# Glove_PCB.net
KiCad netlist of a schematic drawn in Altium Designer
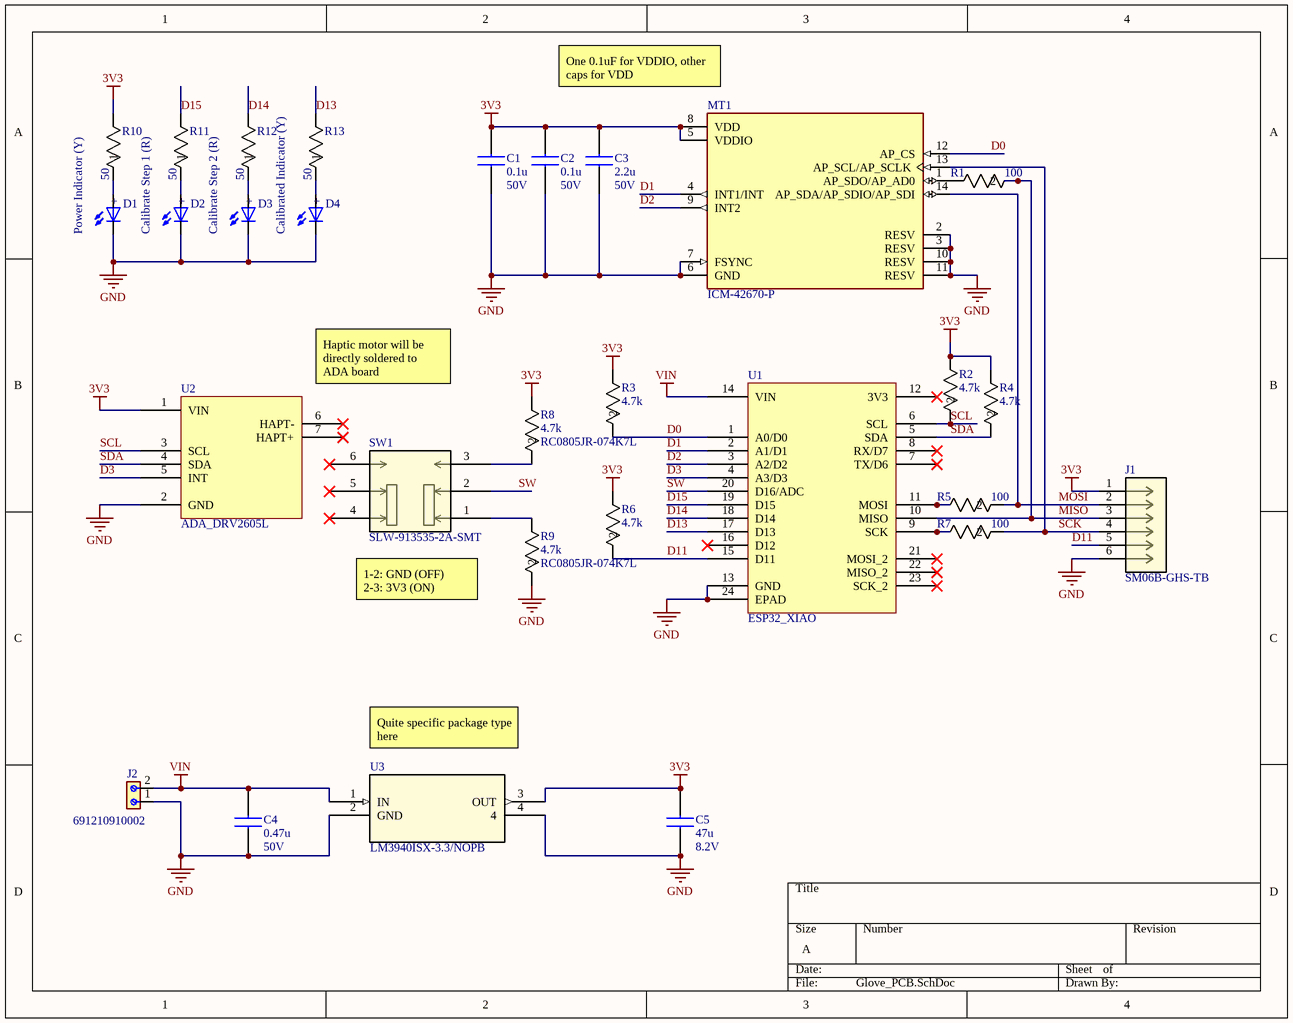
[diagram p0: Glove_PCB.SchDoc]

(export (version "E")
  (design (tool "Eeschema 10.0.6"))
  (components
    (comp (ref "C1")
      (value "0.1u")
      (footprint "CAPC2012X145N")
      (description "Multilayer Ceramic Chip Capacitors, Capacitance=0.1u")
      (fields
        (field (name "MANUFACTURER_PART_NUMBER") "KAM21BR71H104JM")
        (field (name "RATED VOLTAGE") "50V")
      )
      (libsource (lib "Caps") (part "KAM21BR71H104JM"))
    )
    (comp (ref "C2")
      (value "0.1u")
      (footprint "CAPC2012X145N")
      (description "Multilayer Ceramic Chip Capacitors, Capacitance=0.1u")
      (fields
        (field (name "MANUFACTURER_PART_NUMBER") "KAM21BR71H104JM")
        (field (name "RATED VOLTAGE") "50V")
      )
      (libsource (lib "Caps") (part "KAM21BR71H104JM"))
    )
    (comp (ref "C3")
      (value "2.2u")
      (footprint "CAPC2012X145N")
      (description "Multilayer Ceramic Chip Capacitors, Capacitance=2.2u")
      (fields
        (field (name "MANUFACTURER_PART_NUMBER") "C2012X7R1H225K125AE")
        (field (name "RATED VOLTAGE") "50V")
      )
      (libsource (lib "Caps") (part "C2012X7R1H225K125AE"))
    )
    (comp (ref "C4")
      (value "0.47u")
      (footprint "CAPC2012X145N")
      (description "Multilayer Ceramic Chip Capacitors, Capacitance=0.47u")
      (fields
        (field (name "MANUFACTURER_PART_NUMBER") "GCM21BR71H474KA55K")
        (field (name "RATED VOLTAGE") "50V")
      )
      (libsource (lib "Caps") (part "GCM21BR71H474KA55K"))
    )
    (comp (ref "C5")
      (value "47u")
      (footprint "CAPC2012X145N")
      (description "47 µF Molded Tantalum Polymer Capacitor 8.2 V 0805 (2012 Metric) 500mOhm @ 100kHz")
      (fields
        (field (name "MANUFACTURER_PART_NUMBER") "T58W0476M8R2C0500")
        (field (name "RATED VOLTAGE") "8.2V")
      )
      (libsource (lib "Caps") (part "T58W0476M8R2C0500"))
    )
    (comp (ref "D1")
      (value "WL-SMCW_0603")
      (footprint "WL-SMCW_0603")
      (description "0603, Yellow Typ.(@20mA): 590nm, 120mcd, 2.0V, 140Â° AlInGaP")
      (fields (field (name "MF") "Wurth Electronics") (field (name "MP") "150060YS75000"))
      (libsource (lib "WL-SMCW_0603") (part "WL-SMCW_0603"))
    )
    (comp (ref "D2")
      (value "WL-SMCW_0603")
      (footprint "WL-SMCW_0603")
      (description "0603, Super Red Typ.(@20mA): 630nm, 60mcd, 1.9V, 140Â° AlInGaP")
      (fields (field (name "MF") "Wurth Electronics") (field (name "MP") "150060SS75000"))
      (libsource (lib "WL-SMCW_0603") (part "WL-SMCW_0603"))
    )
    (comp (ref "D3")
      (value "WL-SMCW_0603")
      (footprint "WL-SMCW_0603")
      (description "0603, Super Red Typ.(@20mA): 630nm, 60mcd, 1.9V, 140Â° AlInGaP")
      (fields (field (name "MF") "Wurth Electronics") (field (name "MP") "150060SS75000"))
      (libsource (lib "WL-SMCW_0603") (part "WL-SMCW_0603"))
    )
    (comp (ref "D4")
      (value "WL-SMCW_0603")
      (footprint "WL-SMCW_0603")
      (description "0603, Yellow Typ.(@20mA): 590nm, 120mcd, 2.0V, 140Â° AlInGaP")
      (fields (field (name "MF") "Wurth Electronics") (field (name "MP") "150060YS75000"))
      (libsource (lib "WL-SMCW_0603") (part "WL-SMCW_0603"))
    )
    (comp (ref "J1")
      (value "SM06B-GHS-TB")
      (footprint "CONN_SM06B-GHS-TB_JST")
      (description "No Description Available")
      (fields (field (name "COPYRIGHT") "Copyright (C) 2025 Ultra Librarian. All rights reserved."))
      (libsource (lib "SM06B-GHS-TB") (part "SM06B-GHS-TB"))
    )
    (comp (ref "J2")
      (value "691210910002")
      (footprint "691210910002")
      (fields (field (name "MF") "{'manufacturer': u'~{W}xfcrth Elektronik'}"))
      (libsource (lib "691210910002") (part "691210910002"))
    )
    (comp (ref "MT1")
      (value "ICM-42670-P")
      (footprint "XDCR_ICM-42670-P")
      (libsource (lib "ICM-42670-P") (part "ICM-42670-P"))
    )
    (comp (ref "R1")
      (value "100")
      (footprint "RC0805N_YAG")
      (description "RES 0805 100 5% 1/8W")
      (fields (field (name "MANUFACTURER_PART_NUMBER") "RC0805JR-07100RL") (field (name "TOLERANCE") "5%"))
      (libsource (lib "Resistors") (part "RC0805JR-07100RL"))
    )
    (comp (ref "R2")
      (value "4.7k")
      (footprint "RC0805N_YAG")
      (description "RES 0805 4.7k 5% 1/8W")
      (fields (field (name "MANUFACTURER_PART_NUMBER") "RC0805JR-074K7L") (field (name "TOLERANCE") "5%"))
      (libsource (lib "Resistors") (part "RC0805JR-074K7L"))
    )
    (comp (ref "R3")
      (value "4.7k")
      (footprint "RC0805N_YAG")
      (description "RES 0805 4.7k 5% 1/8W")
      (fields (field (name "MANUFACTURER_PART_NUMBER") "RC0805JR-074K7L") (field (name "TOLERANCE") "5%"))
      (libsource (lib "Resistors") (part "RC0805JR-074K7L"))
    )
    (comp (ref "R4")
      (value "4.7k")
      (footprint "RC0805N_YAG")
      (description "RES 0805 4.7k 5% 1/8W")
      (fields (field (name "MANUFACTURER_PART_NUMBER") "RC0805JR-074K7L") (field (name "TOLERANCE") "5%"))
      (libsource (lib "Resistors") (part "RC0805JR-074K7L"))
    )
    (comp (ref "R5")
      (value "100")
      (footprint "RC0805N_YAG")
      (description "RES 0805 100 5% 1/8W")
      (fields (field (name "MANUFACTURER_PART_NUMBER") "RC0805JR-07100RL") (field (name "TOLERANCE") "5%"))
      (libsource (lib "Resistors") (part "RC0805JR-07100RL"))
    )
    (comp (ref "R6")
      (value "4.7k")
      (footprint "RC0805N_YAG")
      (description "RES 0805 4.7k 5% 1/8W")
      (fields (field (name "MANUFACTURER_PART_NUMBER") "RC0805JR-074K7L") (field (name "TOLERANCE") "5%"))
      (libsource (lib "Resistors") (part "RC0805JR-074K7L"))
    )
    (comp (ref "R7")
      (value "100")
      (footprint "RC0805N_YAG")
      (description "RES 0805 100 5% 1/8W")
      (fields (field (name "MANUFACTURER_PART_NUMBER") "RC0805JR-07100RL") (field (name "TOLERANCE") "5%"))
      (libsource (lib "Resistors") (part "RC0805JR-07100RL"))
    )
    (comp (ref "R8")
      (value "RC0805JR-074K7L")
      (footprint "RC0805N_YAG")
      (description "RES 0805 4.7k 5% 1/8W")
      (fields (field (name "TOLERANCE") "5%") (field (name "ALTIUM_VALUE") "4.7k"))
      (libsource (lib "Resistors") (part "RC0805JR-074K7L"))
    )
    (comp (ref "R9")
      (value "RC0805JR-074K7L")
      (footprint "RC0805N_YAG")
      (description "RES 0805 4.7k 5% 1/8W")
      (fields (field (name "TOLERANCE") "5%") (field (name "ALTIUM_VALUE") "4.7k"))
      (libsource (lib "Resistors") (part "RC0805JR-074K7L"))
    )
    (comp (ref "R10")
      (value "50")
      (footprint "RES_RT0603_YAG")
      (description "No Description Available")
      (fields
        (field (name "MANUFACTURER_PART_NUMBER") "RT0603BRD0750RL")
        (field (name "COPYRIGHT") "Copyright (C) 2025 Ultra Librarian. All rights reserved.")
      )
      (libsource (lib "RT0603BRD0750RL") (part "RT0603BRD0750RL"))
    )
    (comp (ref "R11")
      (value "50")
      (footprint "RES_RT0603_YAG")
      (description "No Description Available")
      (fields
        (field (name "MANUFACTURER_PART_NUMBER") "RT0603BRD0750RL")
        (field (name "COPYRIGHT") "Copyright (C) 2025 Ultra Librarian. All rights reserved.")
      )
      (libsource (lib "RT0603BRD0750RL") (part "RT0603BRD0750RL"))
    )
    (comp (ref "R12")
      (value "50")
      (footprint "RES_RT0603_YAG")
      (description "No Description Available")
      (fields
        (field (name "MANUFACTURER_PART_NUMBER") "RT0603BRD0750RL")
        (field (name "COPYRIGHT") "Copyright (C) 2025 Ultra Librarian. All rights reserved.")
      )
      (libsource (lib "RT0603BRD0750RL") (part "RT0603BRD0750RL"))
    )
    (comp (ref "R13")
      (value "50")
      (footprint "RES_RT0603_YAG")
      (description "No Description Available")
      (fields
        (field (name "MANUFACTURER_PART_NUMBER") "RT0603BRD0750RL")
        (field (name "COPYRIGHT") "Copyright (C) 2025 Ultra Librarian. All rights reserved.")
      )
      (libsource (lib "RT0603BRD0750RL") (part "RT0603BRD0750RL"))
    )
    (comp (ref "SW1")
      (value "SLW-913535-2A-SMT")
      (footprint "SLW-913535_CUD")
      (description "No Description Available")
      (fields (field (name "COPYRIGHT") "Copyright (C) 2025 Ultra Librarian. All rights reserved."))
      (libsource (lib "SLW-913535-2A-SMT") (part "SLW-913535-2A-SMT"))
    )
    (comp (ref "U1")
      (value "ESP32_XIAO")
      (footprint "MOUDLE23P-SMD-2.54-21X17.8MM.kicad_mod.kicad_sym")
      (libsource (lib "ESP32") (part "ESP32_XIAO"))
    )
    (comp (ref "U2")
      (value "ADA_DRV2605L")
      (footprint "ADA_DRV2605L")
      (libsource (lib "ADA_DRV2605L") (part "ADA_DRV2605L"))
    )
    (comp (ref "U3")
      (value "LM3940ISX-3.3/NOPB")
      (footprint "TS3B")
      (description "1-A, low-dropout voltage regulator for 5-V to 3.3-V conversion 3-DDPAK/TO-263 -40 to 125")
      (fields (field (name "COPYRIGHT") "Copyright (C) 2025 Ultra Librarian. All rights reserved."))
      (libsource (lib "LM3940ISX-3P3NOPB") (part "LM3940ISX-3.3NOPB"))
    )
  )
  (nets
    (net (code "1") (name "/D0") (class "Default")
      (node (ref "MT1") (pin "12") (pinfunction "AP_CS_12") (pintype "input"))
      (node (ref "R3") (pin "2") (pinfunction "2_2") (pintype "passive"))
      (node (ref "U1") (pin "1") (pinfunction "A0/D0_1") (pintype "passive"))
    )
    (net (code "2") (name "/D1") (class "Default")
      (node (ref "MT1") (pin "4") (pinfunction "INT1/INT_4") (pintype "output"))
      (node (ref "U1") (pin "2") (pinfunction "A1/D1_2") (pintype "passive"))
    )
    (net (code "3") (name "/D2") (class "Default")
      (node (ref "MT1") (pin "9") (pinfunction "INT2_9") (pintype "output"))
      (node (ref "U1") (pin "3") (pinfunction "A2/D2_3") (pintype "passive"))
    )
    (net (code "4") (name "/D3") (class "Default")
      (node (ref "U1") (pin "4") (pinfunction "A3/D3_4") (pintype "passive"))
      (node (ref "U2") (pin "5") (pinfunction "INT_5") (pintype "passive"))
    )
    (net (code "5") (name "/D11") (class "Default")
      (node (ref "J1") (pin "5") (pinfunction "5_5") (pintype "passive"))
      (node (ref "R6") (pin "2") (pinfunction "2_2") (pintype "passive"))
      (node (ref "U1") (pin "15") (pinfunction "D11_15") (pintype "passive"))
    )
    (net (code "6") (name "/D13") (class "Default")
      (node (ref "R13") (pin "2") (pinfunction "2_2") (pintype "passive"))
      (node (ref "U1") (pin "17") (pinfunction "D13_17") (pintype "passive"))
    )
    (net (code "7") (name "/D14") (class "Default")
      (node (ref "R12") (pin "2") (pinfunction "2_2") (pintype "passive"))
      (node (ref "U1") (pin "18") (pinfunction "D14_18") (pintype "passive"))
    )
    (net (code "8") (name "/D15") (class "Default")
      (node (ref "R11") (pin "2") (pinfunction "2_2") (pintype "passive"))
      (node (ref "U1") (pin "19") (pinfunction "D15_19") (pintype "passive"))
    )
    (net (code "9") (name "/MISO") (class "Default")
      (node (ref "J1") (pin "3") (pinfunction "3_3") (pintype "passive"))
      (node (ref "R1") (pin "2") (pinfunction "2_2") (pintype "passive"))
      (node (ref "U1") (pin "10") (pinfunction "MISO_10") (pintype "passive"))
    )
    (net (code "10") (name "/MOSI") (class "Default")
      (node (ref "J1") (pin "2") (pinfunction "2_2") (pintype "passive"))
      (node (ref "MT1") (pin "14") (pinfunction "AP_SDA/AP_SDIO/AP_SDI_14") (pintype "bidirectional"))
      (node (ref "R5") (pin "2") (pinfunction "2_2") (pintype "passive"))
    )
    (net (code "11") (name "/SCK") (class "Default")
      (node (ref "J1") (pin "4") (pinfunction "4_4") (pintype "passive"))
      (node (ref "MT1") (pin "13") (pinfunction "AP_SCL/AP_SCLK_13") (pintype "input"))
      (node (ref "R7") (pin "2") (pinfunction "2_2") (pintype "passive"))
    )
    (net (code "12") (name "/SCL") (class "Default")
      (node (ref "R2") (pin "2") (pinfunction "2_2") (pintype "passive"))
      (node (ref "U1") (pin "6") (pinfunction "SCL_6") (pintype "passive"))
      (node (ref "U2") (pin "3") (pinfunction "SCL_3") (pintype "passive"))
    )
    (net (code "13") (name "/SDA") (class "Default")
      (node (ref "R4") (pin "2") (pinfunction "2_2") (pintype "passive"))
      (node (ref "U1") (pin "5") (pinfunction "SDA_5") (pintype "passive"))
      (node (ref "U2") (pin "4") (pinfunction "SDA_4") (pintype "passive"))
    )
    (net (code "14") (name "/SW") (class "Default")
      (node (ref "SW1") (pin "2") (pinfunction "2_2") (pintype "passive"))
      (node (ref "U1") (pin "20") (pinfunction "D16/ADC_20") (pintype "passive"))
    )
    (net (code "15") (name "3V3") (class "Default")
      (node (ref "C1") (pin "2") (pinfunction "2_2") (pintype "passive"))
      (node (ref "C2") (pin "2") (pinfunction "2_2") (pintype "passive"))
      (node (ref "C3") (pin "2") (pinfunction "2_2") (pintype "passive"))
      (node (ref "C5") (pin "2") (pinfunction "2_2") (pintype "passive"))
      (node (ref "J1") (pin "1") (pinfunction "1_1") (pintype "passive"))
      (node (ref "MT1") (pin "5") (pinfunction "VDDIO_5") (pintype "power_in"))
      (node (ref "MT1") (pin "8") (pinfunction "VDD_8") (pintype "power_in"))
      (node (ref "R10") (pin "2") (pinfunction "2_2") (pintype "passive"))
      (node (ref "R2") (pin "1") (pinfunction "1_1") (pintype "passive"))
      (node (ref "R3") (pin "1") (pinfunction "1_1") (pintype "passive"))
      (node (ref "R4") (pin "1") (pinfunction "1_1") (pintype "passive"))
      (node (ref "R6") (pin "1") (pinfunction "1_1") (pintype "passive"))
      (node (ref "R8") (pin "1") (pinfunction "1_1") (pintype "passive"))
      (node (ref "U2") (pin "1") (pinfunction "VIN_1") (pintype "passive"))
      (node (ref "U3") (pin "3") (pinfunction "OUT_3") (pintype "output"))
    )
    (net (code "16") (name "GND") (class "Default")
      (node (ref "C1") (pin "1") (pinfunction "1_1") (pintype "passive"))
      (node (ref "C2") (pin "1") (pinfunction "1_1") (pintype "passive"))
      (node (ref "C3") (pin "1") (pinfunction "1_1") (pintype "passive"))
      (node (ref "C4") (pin "1") (pinfunction "1_1") (pintype "passive"))
      (node (ref "C5") (pin "1") (pinfunction "1_1") (pintype "passive"))
      (node (ref "D1") (pin "1") (pinfunction "NEG_1") (pintype "passive"))
      (node (ref "D2") (pin "1") (pinfunction "NEG_1") (pintype "passive"))
      (node (ref "D3") (pin "1") (pinfunction "NEG_1") (pintype "passive"))
      (node (ref "D4") (pin "1") (pinfunction "NEG_1") (pintype "passive"))
      (node (ref "J1") (pin "6") (pinfunction "6_6") (pintype "passive"))
      (node (ref "J2") (pin "1") (pinfunction "1_1") (pintype "passive"))
      (node (ref "MT1") (pin "10") (pinfunction "RESV_10") (pintype "passive"))
      (node (ref "MT1") (pin "11") (pinfunction "RESV_11") (pintype "passive"))
      (node (ref "MT1") (pin "2") (pinfunction "RESV_2") (pintype "passive"))
      (node (ref "MT1") (pin "3") (pinfunction "RESV_3") (pintype "passive"))
      (node (ref "MT1") (pin "6") (pinfunction "GND_6") (pintype "power_in"))
      (node (ref "MT1") (pin "7") (pinfunction "FSYNC_7") (pintype "input"))
      (node (ref "R9") (pin "2") (pinfunction "2_2") (pintype "passive"))
      (node (ref "U1") (pin "13") (pinfunction "GND_13") (pintype "passive"))
      (node (ref "U1") (pin "24") (pinfunction "EPAD_24") (pintype "passive"))
      (node (ref "U2") (pin "2") (pinfunction "GND_2") (pintype "passive"))
      (node (ref "U3") (pin "2") (pinfunction "GND_2") (pintype "passive"))
      (node (ref "U3") (pin "4") (pinfunction "4_4") (pintype "passive"))
    )
    (net (code "17") (name "Net-(D1-POS)") (class "Default")
      (node (ref "D1") (pin "2") (pinfunction "POS_2") (pintype "passive"))
      (node (ref "R10") (pin "1") (pinfunction "1_1") (pintype "passive"))
    )
    (net (code "18") (name "Net-(D2-POS)") (class "Default")
      (node (ref "D2") (pin "2") (pinfunction "POS_2") (pintype "passive"))
      (node (ref "R11") (pin "1") (pinfunction "1_1") (pintype "passive"))
    )
    (net (code "19") (name "Net-(D3-POS)") (class "Default")
      (node (ref "D3") (pin "2") (pinfunction "POS_2") (pintype "passive"))
      (node (ref "R12") (pin "1") (pinfunction "1_1") (pintype "passive"))
    )
    (net (code "20") (name "Net-(D4-POS)") (class "Default")
      (node (ref "D4") (pin "2") (pinfunction "POS_2") (pintype "passive"))
      (node (ref "R13") (pin "1") (pinfunction "1_1") (pintype "passive"))
    )
    (net (code "21") (name "Net-(MT1-AP_SDO{slash}AP_AD0)") (class "Default")
      (node (ref "MT1") (pin "1") (pinfunction "AP_SDO/AP_AD0_1") (pintype "bidirectional"))
      (node (ref "R1") (pin "1") (pinfunction "1_1") (pintype "passive"))
    )
    (net (code "22") (name "Net-(R8-Pad2)") (class "Default")
      (node (ref "R8") (pin "2") (pinfunction "2_2") (pintype "passive"))
      (node (ref "SW1") (pin "3") (pinfunction "3_3") (pintype "passive"))
    )
    (net (code "23") (name "Net-(R9-Pad1)") (class "Default")
      (node (ref "R9") (pin "1") (pinfunction "1_1") (pintype "passive"))
      (node (ref "SW1") (pin "1") (pinfunction "1_1") (pintype "passive"))
    )
    (net (code "24") (name "Net-(U1-MOSI)") (class "Default")
      (node (ref "R5") (pin "1") (pinfunction "1_1") (pintype "passive"))
      (node (ref "U1") (pin "11") (pinfunction "MOSI_11") (pintype "passive"))
    )
    (net (code "25") (name "Net-(U1-SCK)") (class "Default")
      (node (ref "R7") (pin "1") (pinfunction "1_1") (pintype "passive"))
      (node (ref "U1") (pin "9") (pinfunction "SCK_9") (pintype "passive"))
    )
    (net (code "26") (name "VIN") (class "Default")
      (node (ref "C4") (pin "2") (pinfunction "2_2") (pintype "passive"))
      (node (ref "J2") (pin "2") (pinfunction "2_2") (pintype "passive"))
      (node (ref "U1") (pin "14") (pinfunction "VIN_14") (pintype "passive"))
      (node (ref "U3") (pin "1") (pinfunction "IN_1") (pintype "input"))
    )
    (net (code "27") (name "unconnected-(SW1-Pad4)") (class "Default")
      (node (ref "SW1") (pin "4") (pinfunction "4_4") (pintype "passive+no_connect"))
    )
    (net (code "28") (name "unconnected-(SW1-Pad5)") (class "Default")
      (node (ref "SW1") (pin "5") (pinfunction "5_5") (pintype "passive+no_connect"))
    )
    (net (code "29") (name "unconnected-(SW1-Pad6)") (class "Default")
      (node (ref "SW1") (pin "6") (pinfunction "6_6") (pintype "passive+no_connect"))
    )
    (net (code "30") (name "unconnected-(U1-3V3-Pad12)") (class "Default")
      (node (ref "U1") (pin "12") (pinfunction "3V3_12") (pintype "passive+no_connect"))
    )
    (net (code "31") (name "unconnected-(U1-D12-Pad16)") (class "Default")
      (node (ref "U1") (pin "16") (pinfunction "D12_16") (pintype "passive+no_connect"))
    )
    (net (code "32") (name "unconnected-(U1-MISO_2-Pad22)") (class "Default")
      (node (ref "U1") (pin "22") (pinfunction "MISO_2_22") (pintype "passive+no_connect"))
    )
    (net (code "33") (name "unconnected-(U1-MOSI_2-Pad21)") (class "Default")
      (node (ref "U1") (pin "21") (pinfunction "MOSI_2_21") (pintype "passive+no_connect"))
    )
    (net (code "34") (name "unconnected-(U1-RX{slash}D7-Pad8)") (class "Default")
      (node (ref "U1") (pin "8") (pinfunction "RX/D7_8") (pintype "passive+no_connect"))
    )
    (net (code "35") (name "unconnected-(U1-SCK_2-Pad23)") (class "Default")
      (node (ref "U1") (pin "23") (pinfunction "SCK_2_23") (pintype "passive+no_connect"))
    )
    (net (code "36") (name "unconnected-(U1-TX{slash}D6-Pad7)") (class "Default")
      (node (ref "U1") (pin "7") (pinfunction "TX/D6_7") (pintype "passive+no_connect"))
    )
    (net (code "37") (name "unconnected-(U2-HAPT+-Pad7)") (class "Default")
      (node (ref "U2") (pin "7") (pinfunction "HAPT+_7") (pintype "passive+no_connect"))
    )
    (net (code "38") (name "unconnected-(U2-HAPT--Pad6)") (class "Default")
      (node (ref "U2") (pin "6") (pinfunction "HAPT-_6") (pintype "passive+no_connect"))
    )
  )
)
